# led_test.net
KiCad netlist of a schematic drawn in Altium Designer
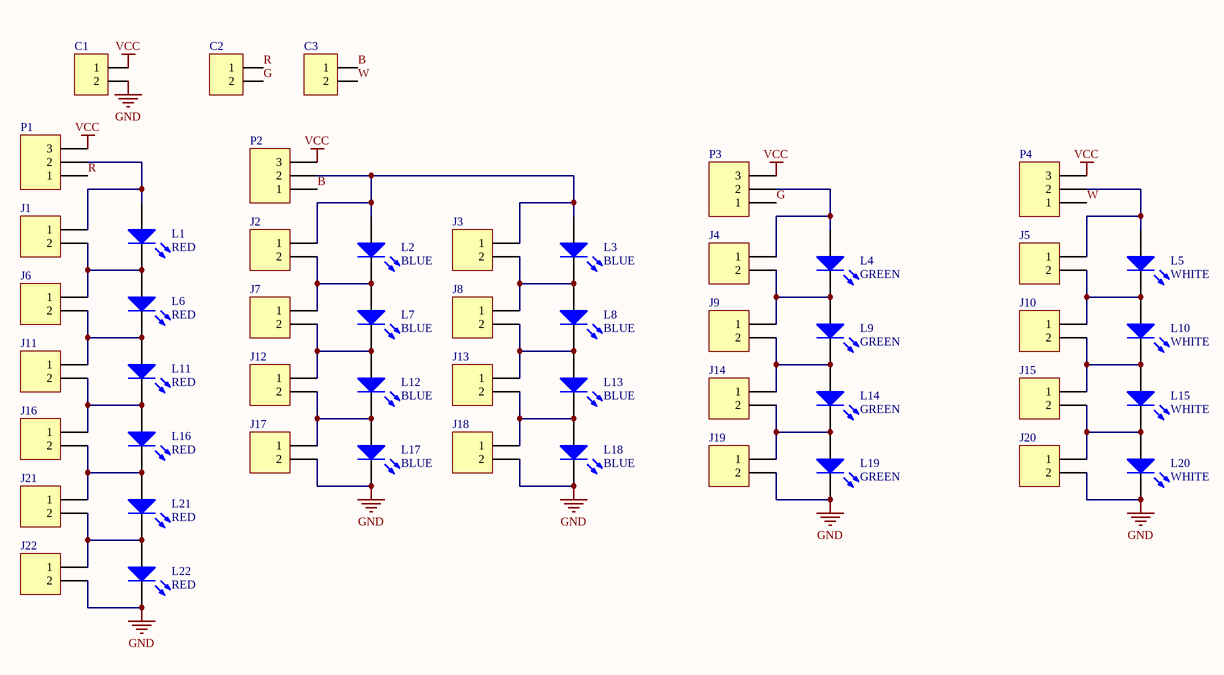
[diagram p0: led_test.SchDoc]

(export (version "E")
  (design (tool "Eeschema 10.0.6"))
  (components
    (comp (ref "C1")
      (value "WE-Terminal Blocks Screw Type 691216510002")
      (footprint "691216510002")
      (description "WR-TBL Terminal block - serie 2165 - 5.08 mm")
      (fields
        (field (name "MANUFACTURER") "Würth Elektronik eiSos GmbH")
        (field (name "PARTNO") "691216510002")
        (field (name "CREATED DATE") "27 Novenber 2013")
        (field (name "CREATED BY") "Karrer Zheng")
      )
      (libsource (lib "WE_WR-TBL_Rising Cage System_5.08 mm_rev15a") (part "WE-Terminal Blocks Screw Type 691216510002"))
    )
    (comp (ref "C2")
      (value "WE-Terminal Blocks Screw Type 691216510002")
      (footprint "691216510002")
      (description "WR-TBL Terminal block - serie 2165 - 5.08 mm")
      (fields
        (field (name "MANUFACTURER") "Würth Elektronik eiSos GmbH")
        (field (name "PARTNO") "691216510002")
        (field (name "CREATED DATE") "27 Novenber 2013")
        (field (name "CREATED BY") "Karrer Zheng")
      )
      (libsource (lib "WE_WR-TBL_Rising Cage System_5.08 mm_rev15a") (part "WE-Terminal Blocks Screw Type 691216510002"))
    )
    (comp (ref "C3")
      (value "WE-Terminal Blocks Screw Type 691216510002")
      (footprint "691216510002")
      (description "WR-TBL Terminal block - serie 2165 - 5.08 mm")
      (fields
        (field (name "MANUFACTURER") "Würth Elektronik eiSos GmbH")
        (field (name "PARTNO") "691216510002")
        (field (name "CREATED DATE") "27 Novenber 2013")
        (field (name "CREATED BY") "Karrer Zheng")
      )
      (libsource (lib "WE_WR-TBL_Rising Cage System_5.08 mm_rev15a") (part "WE-Terminal Blocks Screw Type 691216510002"))
    )
    (comp (ref "J1")
      (value "Header 2")
      (footprint "HDR1X2")
      (description "Header, 2-Pin")
      (fields (field (name "PUBLISHER") "Altium Limited"))
      (libsource (lib "Miscellaneous Connectors") (part "Header 2"))
    )
    (comp (ref "J2")
      (value "Header 2")
      (footprint "HDR1X2")
      (description "Header, 2-Pin")
      (fields (field (name "PUBLISHER") "Altium Limited"))
      (libsource (lib "Miscellaneous Connectors") (part "Header 2"))
    )
    (comp (ref "J3")
      (value "Header 2")
      (footprint "HDR1X2")
      (description "Header, 2-Pin")
      (fields (field (name "PUBLISHER") "Altium Limited"))
      (libsource (lib "Miscellaneous Connectors") (part "Header 2"))
    )
    (comp (ref "J4")
      (value "Header 2")
      (footprint "HDR1X2")
      (description "Header, 2-Pin")
      (fields (field (name "PUBLISHER") "Altium Limited"))
      (libsource (lib "Miscellaneous Connectors") (part "Header 2"))
    )
    (comp (ref "J5")
      (value "Header 2")
      (footprint "HDR1X2")
      (description "Header, 2-Pin")
      (fields (field (name "PUBLISHER") "Altium Limited"))
      (libsource (lib "Miscellaneous Connectors") (part "Header 2"))
    )
    (comp (ref "J6")
      (value "Header 2")
      (footprint "HDR1X2")
      (description "Header, 2-Pin")
      (fields (field (name "PUBLISHER") "Altium Limited"))
      (libsource (lib "Miscellaneous Connectors") (part "Header 2"))
    )
    (comp (ref "J7")
      (value "Header 2")
      (footprint "HDR1X2")
      (description "Header, 2-Pin")
      (fields (field (name "PUBLISHER") "Altium Limited"))
      (libsource (lib "Miscellaneous Connectors") (part "Header 2"))
    )
    (comp (ref "J8")
      (value "Header 2")
      (footprint "HDR1X2")
      (description "Header, 2-Pin")
      (fields (field (name "PUBLISHER") "Altium Limited"))
      (libsource (lib "Miscellaneous Connectors") (part "Header 2"))
    )
    (comp (ref "J9")
      (value "Header 2")
      (footprint "HDR1X2")
      (description "Header, 2-Pin")
      (fields (field (name "PUBLISHER") "Altium Limited"))
      (libsource (lib "Miscellaneous Connectors") (part "Header 2"))
    )
    (comp (ref "J10")
      (value "Header 2")
      (footprint "HDR1X2")
      (description "Header, 2-Pin")
      (fields (field (name "PUBLISHER") "Altium Limited"))
      (libsource (lib "Miscellaneous Connectors") (part "Header 2"))
    )
    (comp (ref "J11")
      (value "Header 2")
      (footprint "HDR1X2")
      (description "Header, 2-Pin")
      (fields (field (name "PUBLISHER") "Altium Limited"))
      (libsource (lib "Miscellaneous Connectors") (part "Header 2"))
    )
    (comp (ref "J12")
      (value "Header 2")
      (footprint "HDR1X2")
      (description "Header, 2-Pin")
      (fields (field (name "PUBLISHER") "Altium Limited"))
      (libsource (lib "Miscellaneous Connectors") (part "Header 2"))
    )
    (comp (ref "J13")
      (value "Header 2")
      (footprint "HDR1X2")
      (description "Header, 2-Pin")
      (fields (field (name "PUBLISHER") "Altium Limited"))
      (libsource (lib "Miscellaneous Connectors") (part "Header 2"))
    )
    (comp (ref "J14")
      (value "Header 2")
      (footprint "HDR1X2")
      (description "Header, 2-Pin")
      (fields (field (name "PUBLISHER") "Altium Limited"))
      (libsource (lib "Miscellaneous Connectors") (part "Header 2"))
    )
    (comp (ref "J15")
      (value "Header 2")
      (footprint "HDR1X2")
      (description "Header, 2-Pin")
      (fields (field (name "PUBLISHER") "Altium Limited"))
      (libsource (lib "Miscellaneous Connectors") (part "Header 2"))
    )
    (comp (ref "J16")
      (value "Header 2")
      (footprint "HDR1X2")
      (description "Header, 2-Pin")
      (fields (field (name "PUBLISHER") "Altium Limited"))
      (libsource (lib "Miscellaneous Connectors") (part "Header 2"))
    )
    (comp (ref "J17")
      (value "Header 2")
      (footprint "HDR1X2")
      (description "Header, 2-Pin")
      (fields (field (name "PUBLISHER") "Altium Limited"))
      (libsource (lib "Miscellaneous Connectors") (part "Header 2"))
    )
    (comp (ref "J18")
      (value "Header 2")
      (footprint "HDR1X2")
      (description "Header, 2-Pin")
      (fields (field (name "PUBLISHER") "Altium Limited"))
      (libsource (lib "Miscellaneous Connectors") (part "Header 2"))
    )
    (comp (ref "J19")
      (value "Header 2")
      (footprint "HDR1X2")
      (description "Header, 2-Pin")
      (fields (field (name "PUBLISHER") "Altium Limited"))
      (libsource (lib "Miscellaneous Connectors") (part "Header 2"))
    )
    (comp (ref "J20")
      (value "Header 2")
      (footprint "HDR1X2")
      (description "Header, 2-Pin")
      (fields (field (name "PUBLISHER") "Altium Limited"))
      (libsource (lib "Miscellaneous Connectors") (part "Header 2"))
    )
    (comp (ref "J21")
      (value "Header 2")
      (footprint "HDR1X2")
      (description "Header, 2-Pin")
      (fields (field (name "PUBLISHER") "Altium Limited"))
      (libsource (lib "Miscellaneous Connectors") (part "Header 2"))
    )
    (comp (ref "J22")
      (value "Header 2")
      (footprint "HDR1X2")
      (description "Header, 2-Pin")
      (fields (field (name "PUBLISHER") "Altium Limited"))
      (libsource (lib "Miscellaneous Connectors") (part "Header 2"))
    )
    (comp (ref "L1")
      (value "RED")
      (footprint "1W LED")
      (libsource (lib "Miscellaneous Devices") (part "LED2"))
    )
    (comp (ref "L2")
      (value "BLUE")
      (footprint "1W LED")
      (libsource (lib "Miscellaneous Devices") (part "LED2"))
    )
    (comp (ref "L3")
      (value "BLUE")
      (footprint "1W LED")
      (libsource (lib "Miscellaneous Devices") (part "LED2"))
    )
    (comp (ref "L4")
      (value "GREEN")
      (footprint "1W LED")
      (libsource (lib "Miscellaneous Devices") (part "LED2"))
    )
    (comp (ref "L5")
      (value "WHITE")
      (footprint "1W LED")
      (libsource (lib "Miscellaneous Devices") (part "LED2"))
    )
    (comp (ref "L6")
      (value "RED")
      (footprint "1W LED")
      (libsource (lib "Miscellaneous Devices") (part "LED2"))
    )
    (comp (ref "L7")
      (value "BLUE")
      (footprint "1W LED")
      (libsource (lib "Miscellaneous Devices") (part "LED2"))
    )
    (comp (ref "L8")
      (value "BLUE")
      (footprint "1W LED")
      (libsource (lib "Miscellaneous Devices") (part "LED2"))
    )
    (comp (ref "L9")
      (value "GREEN")
      (footprint "1W LED")
      (libsource (lib "Miscellaneous Devices") (part "LED2"))
    )
    (comp (ref "L10")
      (value "WHITE")
      (footprint "1W LED")
      (libsource (lib "Miscellaneous Devices") (part "LED2"))
    )
    (comp (ref "L11")
      (value "RED")
      (footprint "1W LED")
      (libsource (lib "Miscellaneous Devices") (part "LED2"))
    )
    (comp (ref "L12")
      (value "BLUE")
      (footprint "1W LED")
      (libsource (lib "Miscellaneous Devices") (part "LED2"))
    )
    (comp (ref "L13")
      (value "BLUE")
      (footprint "1W LED")
      (libsource (lib "Miscellaneous Devices") (part "LED2"))
    )
    (comp (ref "L14")
      (value "GREEN")
      (footprint "1W LED")
      (libsource (lib "Miscellaneous Devices") (part "LED2"))
    )
    (comp (ref "L15")
      (value "WHITE")
      (footprint "1W LED")
      (libsource (lib "Miscellaneous Devices") (part "LED2"))
    )
    (comp (ref "L16")
      (value "RED")
      (footprint "1W LED")
      (libsource (lib "Miscellaneous Devices") (part "LED2"))
    )
    (comp (ref "L17")
      (value "BLUE")
      (footprint "1W LED")
      (libsource (lib "Miscellaneous Devices") (part "LED2"))
    )
    (comp (ref "L18")
      (value "BLUE")
      (footprint "1W LED")
      (libsource (lib "Miscellaneous Devices") (part "LED2"))
    )
    (comp (ref "L19")
      (value "GREEN")
      (footprint "1W LED")
      (libsource (lib "Miscellaneous Devices") (part "LED2"))
    )
    (comp (ref "L20")
      (value "WHITE")
      (footprint "1W LED")
      (libsource (lib "Miscellaneous Devices") (part "LED2"))
    )
    (comp (ref "L21")
      (value "RED")
      (footprint "1W LED")
      (libsource (lib "Miscellaneous Devices") (part "LED2"))
    )
    (comp (ref "L22")
      (value "RED")
      (footprint "1W LED")
      (libsource (lib "Miscellaneous Devices") (part "LED2"))
    )
    (comp (ref "P1")
      (value "Header 3")
      (footprint "HDR1X3")
      (description "Header, 3-Pin")
      (fields (field (name "PUBLISHER") "Altium Limited"))
      (libsource (lib "Miscellaneous Connectors") (part "Header 3"))
    )
    (comp (ref "P2")
      (value "Header 3")
      (footprint "HDR1X3")
      (description "Header, 3-Pin")
      (fields (field (name "PUBLISHER") "Altium Limited"))
      (libsource (lib "Miscellaneous Connectors") (part "Header 3"))
    )
    (comp (ref "P3")
      (value "Header 3")
      (footprint "HDR1X3")
      (description "Header, 3-Pin")
      (fields (field (name "PUBLISHER") "Altium Limited"))
      (libsource (lib "Miscellaneous Connectors") (part "Header 3"))
    )
    (comp (ref "P4")
      (value "Header 3")
      (footprint "HDR1X3")
      (description "Header, 3-Pin")
      (fields (field (name "PUBLISHER") "Altium Limited"))
      (libsource (lib "Miscellaneous Connectors") (part "Header 3"))
    )
  )
  (nets
    (net (code "1") (name "/B") (class "Default")
      (node (ref "C3") (pin "1") (pinfunction "1_1") (pintype "passive"))
      (node (ref "P2") (pin "1") (pinfunction "1_1") (pintype "passive"))
    )
    (net (code "2") (name "/G") (class "Default")
      (node (ref "C2") (pin "2") (pinfunction "2_2") (pintype "passive"))
      (node (ref "P3") (pin "1") (pinfunction "1_1") (pintype "passive"))
    )
    (net (code "3") (name "/R") (class "Default")
      (node (ref "C2") (pin "1") (pinfunction "1_1") (pintype "passive"))
      (node (ref "P1") (pin "1") (pinfunction "1_1") (pintype "passive"))
    )
    (net (code "4") (name "/W") (class "Default")
      (node (ref "C3") (pin "2") (pinfunction "2_2") (pintype "passive"))
      (node (ref "P4") (pin "1") (pinfunction "1_1") (pintype "passive"))
    )
    (net (code "5") (name "GND") (class "Default")
      (node (ref "C1") (pin "2") (pinfunction "2_2") (pintype "passive"))
      (node (ref "J17") (pin "2") (pinfunction "2_2") (pintype "passive"))
      (node (ref "J18") (pin "2") (pinfunction "2_2") (pintype "passive"))
      (node (ref "J19") (pin "2") (pinfunction "2_2") (pintype "passive"))
      (node (ref "J20") (pin "2") (pinfunction "2_2") (pintype "passive"))
      (node (ref "J22") (pin "2") (pinfunction "2_2") (pintype "passive"))
      (node (ref "L17") (pin "2") (pinfunction "K_2") (pintype "passive"))
      (node (ref "L18") (pin "2") (pinfunction "K_2") (pintype "passive"))
      (node (ref "L19") (pin "2") (pinfunction "K_2") (pintype "passive"))
      (node (ref "L20") (pin "2") (pinfunction "K_2") (pintype "passive"))
      (node (ref "L22") (pin "2") (pinfunction "K_2") (pintype "passive"))
    )
    (net (code "6") (name "Net-(L1-A)") (class "Default")
      (node (ref "J1") (pin "1") (pinfunction "1_1") (pintype "passive"))
      (node (ref "L1") (pin "1") (pinfunction "A_1") (pintype "passive"))
      (node (ref "P1") (pin "2") (pinfunction "2_2") (pintype "passive"))
    )
    (net (code "7") (name "Net-(L1-K)") (class "Default")
      (node (ref "J1") (pin "2") (pinfunction "2_2") (pintype "passive"))
      (node (ref "J6") (pin "1") (pinfunction "1_1") (pintype "passive"))
      (node (ref "L1") (pin "2") (pinfunction "K_2") (pintype "passive"))
      (node (ref "L6") (pin "1") (pinfunction "A_1") (pintype "passive"))
    )
    (net (code "8") (name "Net-(L2-A)") (class "Default")
      (node (ref "J2") (pin "1") (pinfunction "1_1") (pintype "passive"))
      (node (ref "J3") (pin "1") (pinfunction "1_1") (pintype "passive"))
      (node (ref "L2") (pin "1") (pinfunction "A_1") (pintype "passive"))
      (node (ref "L3") (pin "1") (pinfunction "A_1") (pintype "passive"))
      (node (ref "P2") (pin "2") (pinfunction "2_2") (pintype "passive"))
    )
    (net (code "9") (name "Net-(L2-K)") (class "Default")
      (node (ref "J2") (pin "2") (pinfunction "2_2") (pintype "passive"))
      (node (ref "J7") (pin "1") (pinfunction "1_1") (pintype "passive"))
      (node (ref "L2") (pin "2") (pinfunction "K_2") (pintype "passive"))
      (node (ref "L7") (pin "1") (pinfunction "A_1") (pintype "passive"))
    )
    (net (code "10") (name "Net-(L3-K)") (class "Default")
      (node (ref "J3") (pin "2") (pinfunction "2_2") (pintype "passive"))
      (node (ref "J8") (pin "1") (pinfunction "1_1") (pintype "passive"))
      (node (ref "L3") (pin "2") (pinfunction "K_2") (pintype "passive"))
      (node (ref "L8") (pin "1") (pinfunction "A_1") (pintype "passive"))
    )
    (net (code "11") (name "Net-(L4-A)") (class "Default")
      (node (ref "J4") (pin "1") (pinfunction "1_1") (pintype "passive"))
      (node (ref "L4") (pin "1") (pinfunction "A_1") (pintype "passive"))
      (node (ref "P3") (pin "2") (pinfunction "2_2") (pintype "passive"))
    )
    (net (code "12") (name "Net-(L4-K)") (class "Default")
      (node (ref "J4") (pin "2") (pinfunction "2_2") (pintype "passive"))
      (node (ref "J9") (pin "1") (pinfunction "1_1") (pintype "passive"))
      (node (ref "L4") (pin "2") (pinfunction "K_2") (pintype "passive"))
      (node (ref "L9") (pin "1") (pinfunction "A_1") (pintype "passive"))
    )
    (net (code "13") (name "Net-(L5-A)") (class "Default")
      (node (ref "J5") (pin "1") (pinfunction "1_1") (pintype "passive"))
      (node (ref "L5") (pin "1") (pinfunction "A_1") (pintype "passive"))
      (node (ref "P4") (pin "2") (pinfunction "2_2") (pintype "passive"))
    )
    (net (code "14") (name "Net-(L10-A)") (class "Default")
      (node (ref "J10") (pin "1") (pinfunction "1_1") (pintype "passive"))
      (node (ref "J5") (pin "2") (pinfunction "2_2") (pintype "passive"))
      (node (ref "L10") (pin "1") (pinfunction "A_1") (pintype "passive"))
      (node (ref "L5") (pin "2") (pinfunction "K_2") (pintype "passive"))
    )
    (net (code "15") (name "Net-(L10-K)") (class "Default")
      (node (ref "J10") (pin "2") (pinfunction "2_2") (pintype "passive"))
      (node (ref "J15") (pin "1") (pinfunction "1_1") (pintype "passive"))
      (node (ref "L10") (pin "2") (pinfunction "K_2") (pintype "passive"))
      (node (ref "L15") (pin "1") (pinfunction "A_1") (pintype "passive"))
    )
    (net (code "16") (name "Net-(L11-A)") (class "Default")
      (node (ref "J11") (pin "1") (pinfunction "1_1") (pintype "passive"))
      (node (ref "J6") (pin "2") (pinfunction "2_2") (pintype "passive"))
      (node (ref "L11") (pin "1") (pinfunction "A_1") (pintype "passive"))
      (node (ref "L6") (pin "2") (pinfunction "K_2") (pintype "passive"))
    )
    (net (code "17") (name "Net-(L11-K)") (class "Default")
      (node (ref "J11") (pin "2") (pinfunction "2_2") (pintype "passive"))
      (node (ref "J16") (pin "1") (pinfunction "1_1") (pintype "passive"))
      (node (ref "L11") (pin "2") (pinfunction "K_2") (pintype "passive"))
      (node (ref "L16") (pin "1") (pinfunction "A_1") (pintype "passive"))
    )
    (net (code "18") (name "Net-(L12-A)") (class "Default")
      (node (ref "J12") (pin "1") (pinfunction "1_1") (pintype "passive"))
      (node (ref "J7") (pin "2") (pinfunction "2_2") (pintype "passive"))
      (node (ref "L12") (pin "1") (pinfunction "A_1") (pintype "passive"))
      (node (ref "L7") (pin "2") (pinfunction "K_2") (pintype "passive"))
    )
    (net (code "19") (name "Net-(L12-K)") (class "Default")
      (node (ref "J12") (pin "2") (pinfunction "2_2") (pintype "passive"))
      (node (ref "J17") (pin "1") (pinfunction "1_1") (pintype "passive"))
      (node (ref "L12") (pin "2") (pinfunction "K_2") (pintype "passive"))
      (node (ref "L17") (pin "1") (pinfunction "A_1") (pintype "passive"))
    )
    (net (code "20") (name "Net-(L13-A)") (class "Default")
      (node (ref "J13") (pin "1") (pinfunction "1_1") (pintype "passive"))
      (node (ref "J8") (pin "2") (pinfunction "2_2") (pintype "passive"))
      (node (ref "L13") (pin "1") (pinfunction "A_1") (pintype "passive"))
      (node (ref "L8") (pin "2") (pinfunction "K_2") (pintype "passive"))
    )
    (net (code "21") (name "Net-(L13-K)") (class "Default")
      (node (ref "J13") (pin "2") (pinfunction "2_2") (pintype "passive"))
      (node (ref "J18") (pin "1") (pinfunction "1_1") (pintype "passive"))
      (node (ref "L13") (pin "2") (pinfunction "K_2") (pintype "passive"))
      (node (ref "L18") (pin "1") (pinfunction "A_1") (pintype "passive"))
    )
    (net (code "22") (name "Net-(L14-A)") (class "Default")
      (node (ref "J14") (pin "1") (pinfunction "1_1") (pintype "passive"))
      (node (ref "J9") (pin "2") (pinfunction "2_2") (pintype "passive"))
      (node (ref "L14") (pin "1") (pinfunction "A_1") (pintype "passive"))
      (node (ref "L9") (pin "2") (pinfunction "K_2") (pintype "passive"))
    )
    (net (code "23") (name "Net-(L14-K)") (class "Default")
      (node (ref "J14") (pin "2") (pinfunction "2_2") (pintype "passive"))
      (node (ref "J19") (pin "1") (pinfunction "1_1") (pintype "passive"))
      (node (ref "L14") (pin "2") (pinfunction "K_2") (pintype "passive"))
      (node (ref "L19") (pin "1") (pinfunction "A_1") (pintype "passive"))
    )
    (net (code "24") (name "Net-(L15-K)") (class "Default")
      (node (ref "J15") (pin "2") (pinfunction "2_2") (pintype "passive"))
      (node (ref "J20") (pin "1") (pinfunction "1_1") (pintype "passive"))
      (node (ref "L15") (pin "2") (pinfunction "K_2") (pintype "passive"))
      (node (ref "L20") (pin "1") (pinfunction "A_1") (pintype "passive"))
    )
    (net (code "25") (name "Net-(L16-K)") (class "Default")
      (node (ref "J16") (pin "2") (pinfunction "2_2") (pintype "passive"))
      (node (ref "J21") (pin "1") (pinfunction "1_1") (pintype "passive"))
      (node (ref "L16") (pin "2") (pinfunction "K_2") (pintype "passive"))
      (node (ref "L21") (pin "1") (pinfunction "A_1") (pintype "passive"))
    )
    (net (code "26") (name "Net-(L21-K)") (class "Default")
      (node (ref "J21") (pin "2") (pinfunction "2_2") (pintype "passive"))
      (node (ref "J22") (pin "1") (pinfunction "1_1") (pintype "passive"))
      (node (ref "L21") (pin "2") (pinfunction "K_2") (pintype "passive"))
      (node (ref "L22") (pin "1") (pinfunction "A_1") (pintype "passive"))
    )
    (net (code "27") (name "VCC") (class "Default")
      (node (ref "C1") (pin "1") (pinfunction "1_1") (pintype "passive"))
      (node (ref "P1") (pin "3") (pinfunction "3_3") (pintype "passive"))
      (node (ref "P2") (pin "3") (pinfunction "3_3") (pintype "passive"))
      (node (ref "P3") (pin "3") (pinfunction "3_3") (pintype "passive"))
      (node (ref "P4") (pin "3") (pinfunction "3_3") (pintype "passive"))
    )
  )
)
